# P15-EXP_IO.net
KiCad netlist of a schematic drawn in Altium Designer
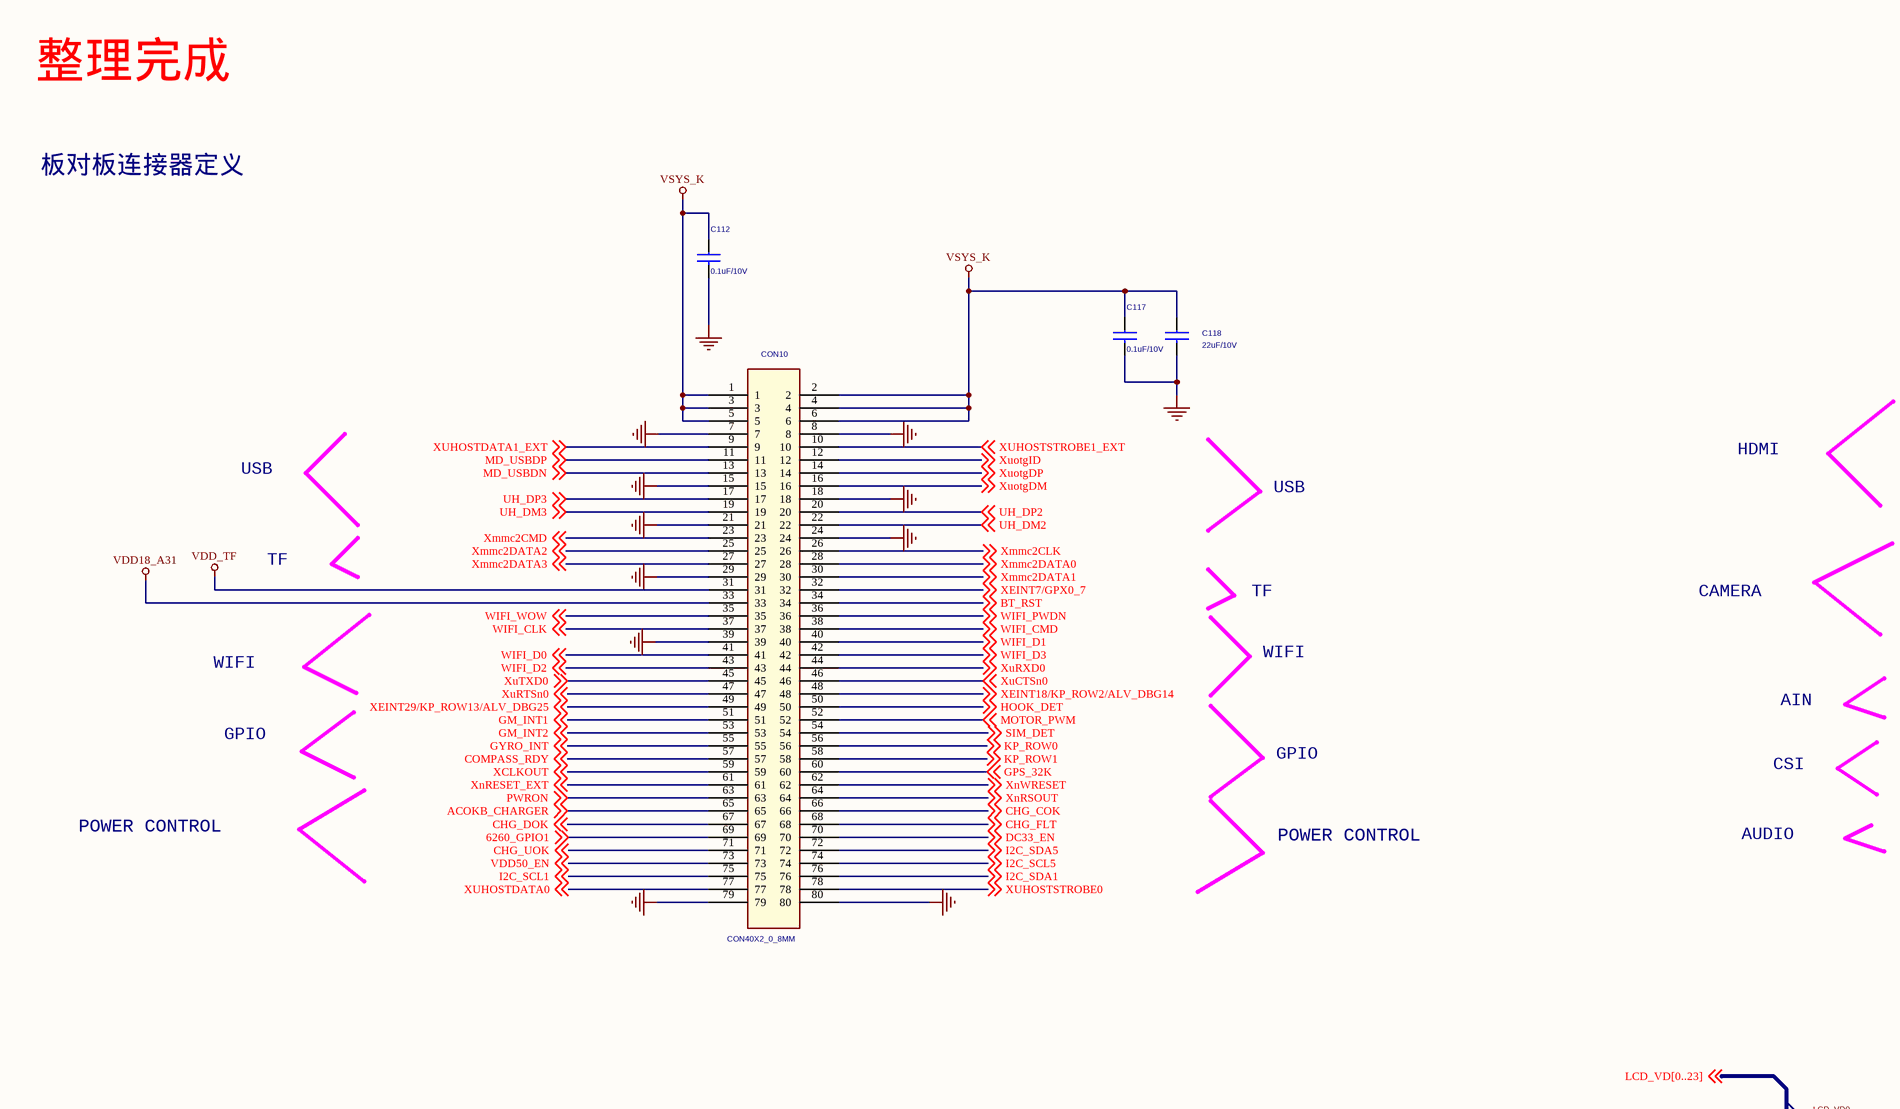
[diagram p0: P15-EXP_IO.SchDoc, top left]
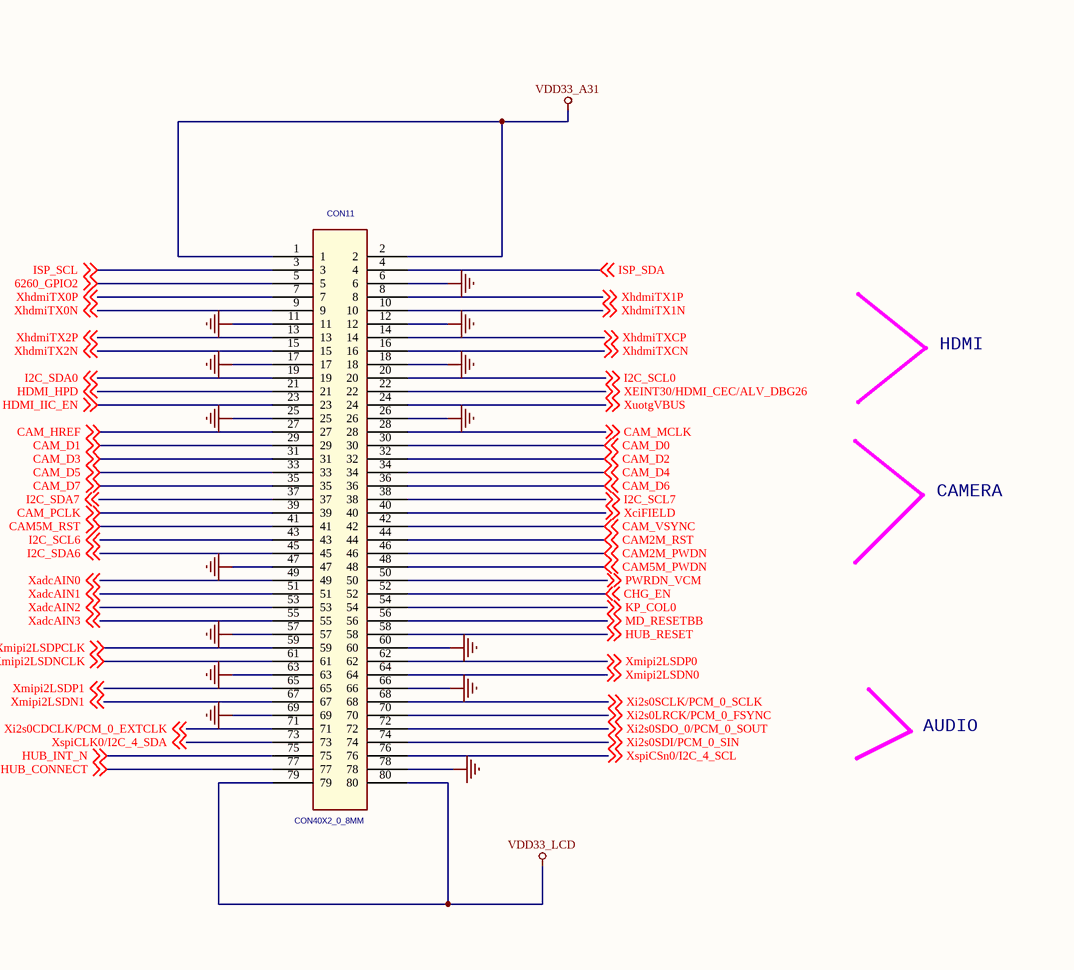
[diagram p1: P15-EXP_IO.SchDoc, top right]
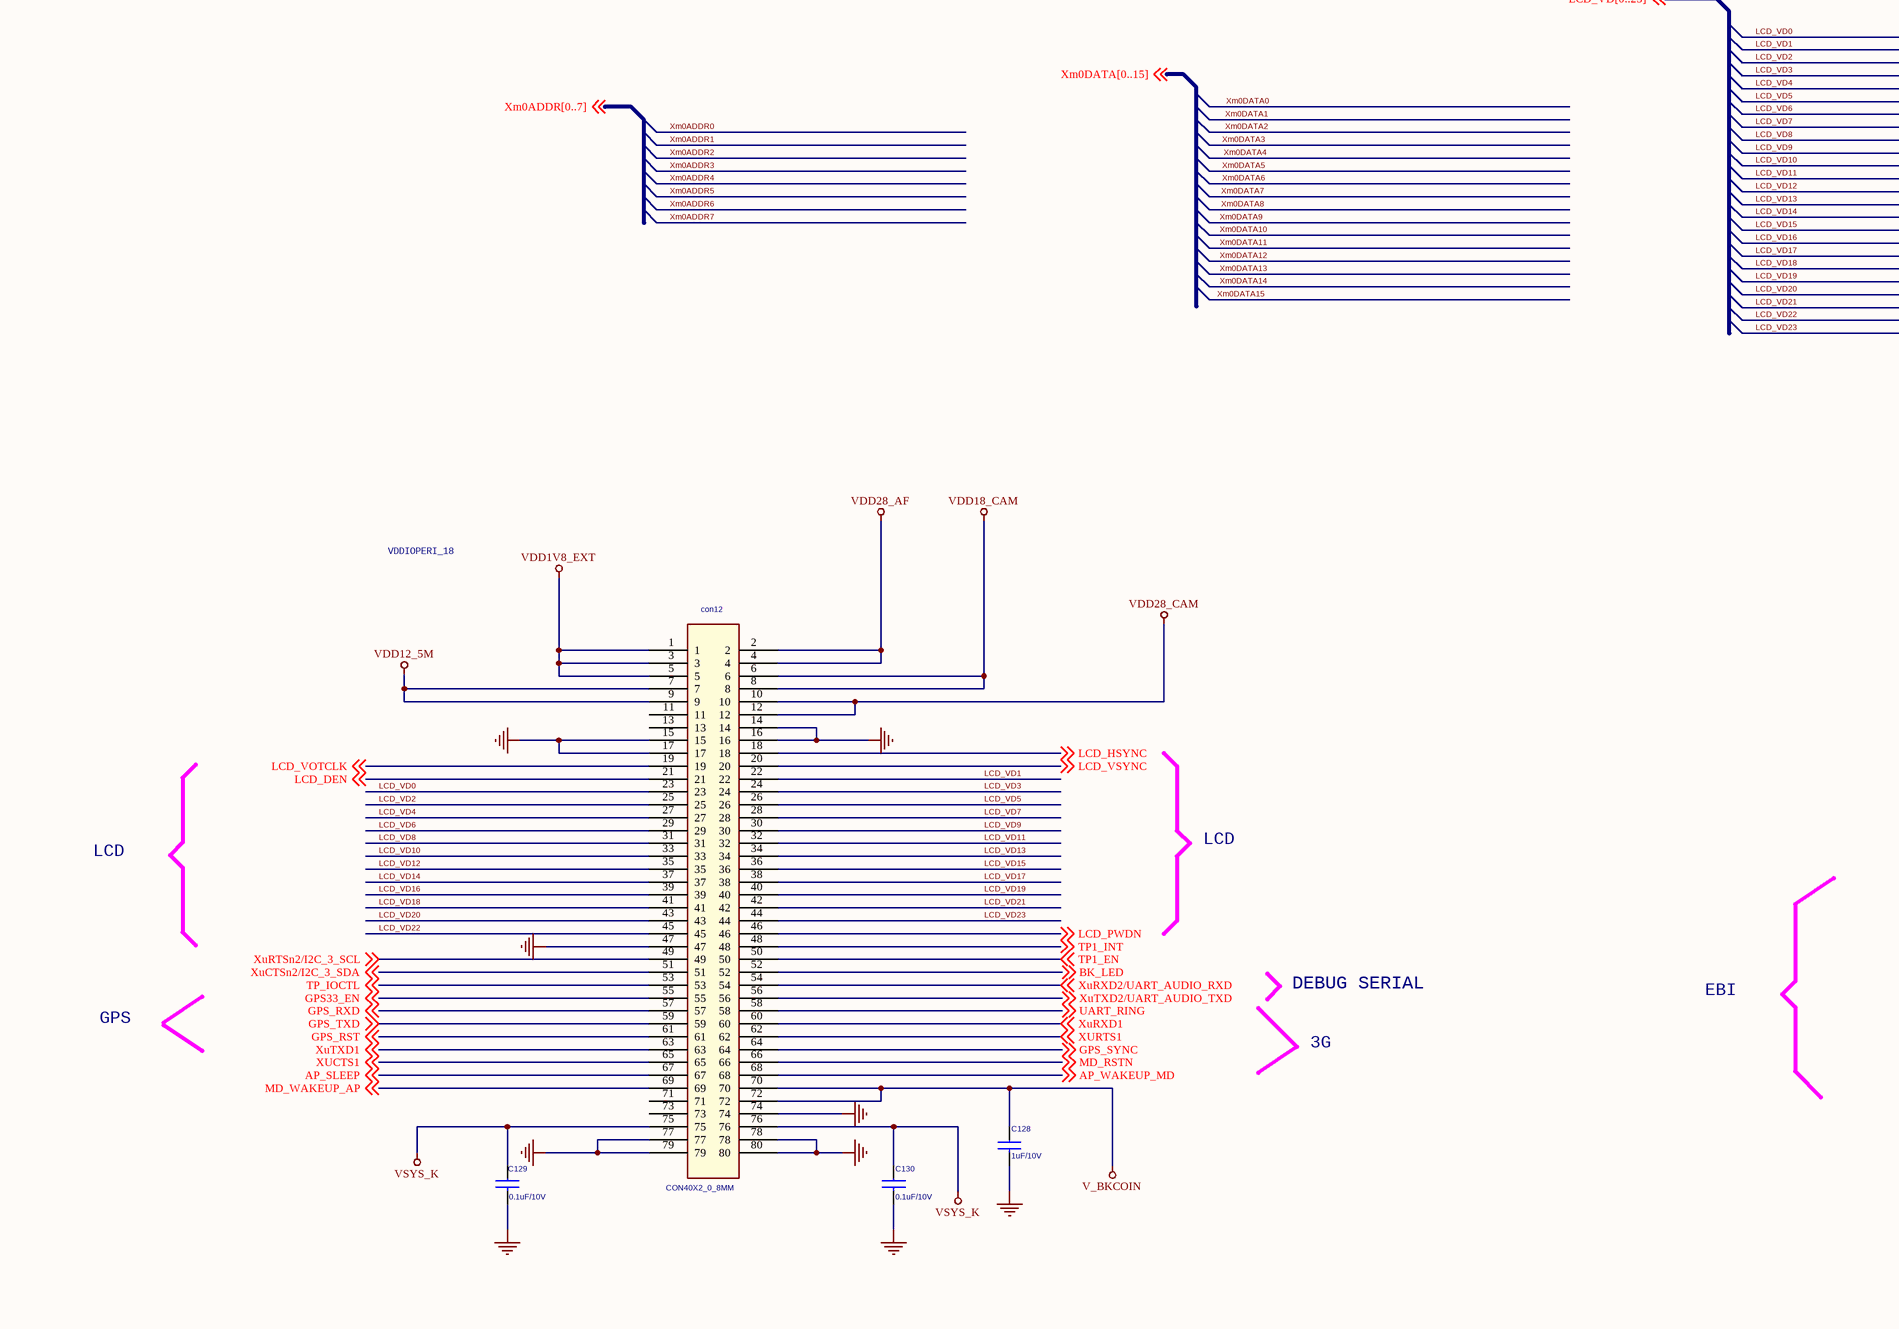
[diagram p2: P15-EXP_IO.SchDoc, bottom left]
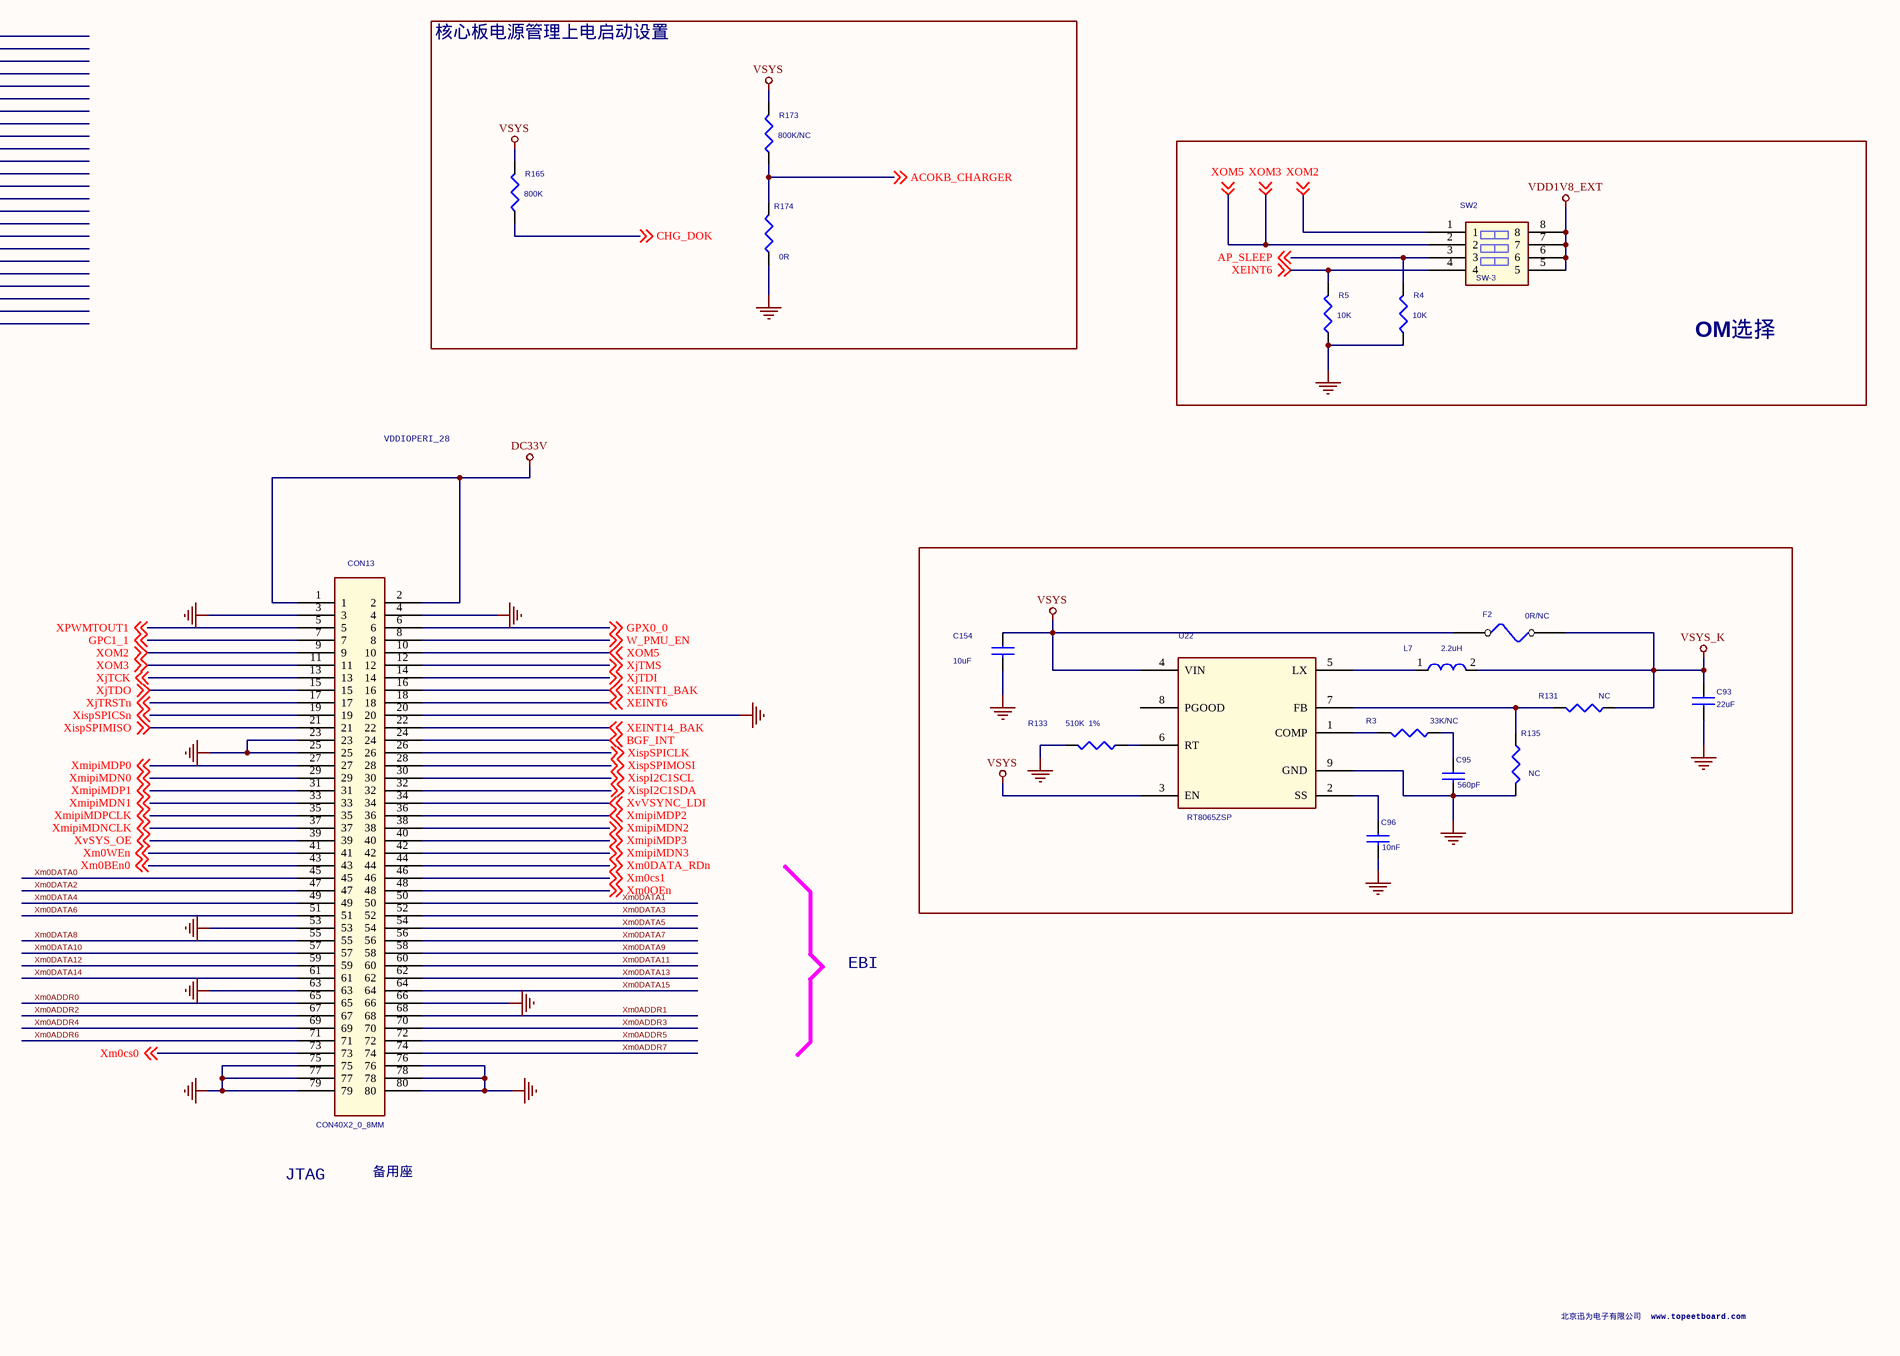
[diagram p3: P15-EXP_IO.SchDoc, bottom right]

(export (version "E")
  (design (tool "Eeschema 10.0.6"))
  (components
    (comp (ref "C93") (value "22uF") (footprint "C0805-S") (libsource (lib "*") (part "C1005")))
    (comp (ref "C95")
      (value "560pF")
      (footprint "C0603-S")
      (description "CER CHIP 1U 10% X5R 0402 10V  L/F")
      (fields (field (name "PART_NUMBER") "06-210594-01"))
      (libsource (lib "*") (part "CAP NP_3"))
    )
    (comp (ref "C96")
      (value "10nF")
      (footprint "C0603-S")
      (description "CER CHIP 1U 10% X5R 0402 10V  L/F")
      (fields (field (name "PART_NUMBER") "06-210594-01"))
      (libsource (lib "*") (part "CAP NP_3"))
    )
    (comp (ref "C112") (value "0.1uF/10V") (footprint "C0603-S") (libsource (lib "*") (part "C0402_0")))
    (comp (ref "C117") (value "0.1uF/10V") (footprint "C0603-S") (libsource (lib "*") (part "C0402_0")))
    (comp (ref "C118") (value "22uF/10V") (footprint "C1206-S") (libsource (lib "*") (part "C1206_0")))
    (comp (ref "C128") (value "1uF/10V") (footprint "C0603-S") (libsource (lib "*") (part "C0603_0")))
    (comp (ref "C129") (value "0.1uF/10V") (footprint "C0603-S") (libsource (lib "*") (part "C0402_0")))
    (comp (ref "C130") (value "0.1uF/10V") (footprint "C0603-S") (libsource (lib "*") (part "C0402_0")))
    (comp (ref "C154")
      (value "10uF")
      (footprint "C0603-S")
      (description "CER CHIP 1U 10% X5R 0402 10V  L/F")
      (fields (field (name "PART_NUMBER") "06-210594-01"))
      (libsource (lib "*") (part "CAP NP_3"))
    )
    (comp (ref "CON10") (value "CON40X2_0_8MM") (libsource (lib "*") (part "CON40X2_0_8MM")))
    (comp (ref "CON11") (value "CON40X2_0_8MM") (libsource (lib "*") (part "CON40X2_0_8MM")))
    (comp (ref "con12")
      (value "CON40X2_0_8MM")
      (footprint "CON2X40-0_5MM-BB")
      (libsource (lib "*") (part "CON40X2_0_8MM"))
    )
    (comp (ref "CON13") (value "CON40X2_0_8MM") (libsource (lib "*") (part "CON40X2_0_8MM")))
    (comp (ref "F2") (value "0R/NC") (libsource (lib "*") (part "FUSE")))
    (comp (ref "L7") (value "2.2uH") (footprint "L3X3MM") (libsource (lib "*") (part "LQH32C_0")))
    (comp (ref "R3") (value "33K/NC") (footprint "R0603-S") (libsource (lib "*") (part "R1005_0")))
    (comp (ref "R4") (value "10K") (footprint "R0603-S") (libsource (lib "*") (part "R1005_0_Dup1")))
    (comp (ref "R5") (value "10K") (footprint "R0603-S") (libsource (lib "*") (part "R1005_0_Dup1")))
    (comp (ref "R131") (value "NC") (footprint "R0603-S") (libsource (lib "*") (part "R1005_0")))
    (comp (ref "R133") (value "510K  1%") (footprint "R0603-S") (libsource (lib "*") (part "R1005_0")))
    (comp (ref "R135") (value "NC") (footprint "R0603-S") (libsource (lib "*") (part "R1005_0")))
    (comp (ref "R165") (value "800K") (footprint "R0603-S") (libsource (lib "*") (part "R1005_0_Dup1")))
    (comp (ref "R173") (value "800K/NC") (footprint "R0603-S") (libsource (lib "*") (part "R1005_0_Dup1")))
    (comp (ref "R174") (value "0R") (footprint "R0603-S") (libsource (lib "*") (part "R1005_0_Dup1")))
    (comp (ref "SW2") (value "SW-3") (libsource (lib "*") (part "SW-3_1")))
    (comp (ref "U22") (value "RT8065ZSP") (libsource (lib "*") (part "RT8065_3")))
  )
  (nets
    (net (code "1") (name "6260_GPIO1") (class "Default")
      (node (ref "CON10") (pin "69") (pinfunction "69_69") (pintype "passive"))
    )
    (net (code "2") (name "6260_GPIO2") (class "Default")
      (node (ref "CON11") (pin "5") (pinfunction "5_5") (pintype "passive"))
    )
    (net (code "3") (name "ACOKB_CHARGER") (class "Default")
      (node (ref "CON10") (pin "65") (pinfunction "65_65") (pintype "passive"))
      (node (ref "R173") (pin "1") (pinfunction "1_1") (pintype "passive"))
      (node (ref "R174") (pin "2") (pinfunction "2_2") (pintype "passive"))
    )
    (net (code "4") (name "AP_SLEEP") (class "Default")
      (node (ref "R4") (pin "2") (pinfunction "2_2") (pintype "passive"))
      (node (ref "SW2") (pin "3") (pinfunction "3_3") (pintype "passive"))
      (node (ref "con12") (pin "67") (pinfunction "67_67") (pintype "passive"))
    )
    (net (code "5") (name "AP_WAKEUP_MD") (class "Default")
      (node (ref "con12") (pin "68") (pinfunction "68_68") (pintype "passive"))
    )
    (net (code "6") (name "BGF_INT") (class "Default")
      (node (ref "CON13") (pin "24") (pinfunction "24_24") (pintype "passive"))
    )
    (net (code "7") (name "BK_LED") (class "Default")
      (node (ref "con12") (pin "52") (pinfunction "52_52") (pintype "passive"))
    )
    (net (code "8") (name "BT_RST") (class "Default")
      (node (ref "CON10") (pin "34") (pinfunction "34_34") (pintype "passive"))
    )
    (net (code "9") (name "CAM2M_PWDN") (class "Default")
      (node (ref "CON11") (pin "46") (pinfunction "46_46") (pintype "passive"))
    )
    (net (code "10") (name "CAM2M_RST") (class "Default")
      (node (ref "CON11") (pin "44") (pinfunction "44_44") (pintype "passive"))
    )
    (net (code "11") (name "CAM5M_PWDN") (class "Default")
      (node (ref "CON11") (pin "48") (pinfunction "48_48") (pintype "passive"))
    )
    (net (code "12") (name "CAM5M_RST") (class "Default")
      (node (ref "CON11") (pin "41") (pinfunction "41_41") (pintype "passive"))
    )
    (net (code "13") (name "CAM_D0") (class "Default")
      (node (ref "CON11") (pin "30") (pinfunction "30_30") (pintype "passive"))
    )
    (net (code "14") (name "CAM_D1") (class "Default")
      (node (ref "CON11") (pin "29") (pinfunction "29_29") (pintype "passive"))
    )
    (net (code "15") (name "CAM_D2") (class "Default")
      (node (ref "CON11") (pin "32") (pinfunction "32_32") (pintype "passive"))
    )
    (net (code "16") (name "CAM_D3") (class "Default")
      (node (ref "CON11") (pin "31") (pinfunction "31_31") (pintype "passive"))
    )
    (net (code "17") (name "CAM_D4") (class "Default")
      (node (ref "CON11") (pin "34") (pinfunction "34_34") (pintype "passive"))
    )
    (net (code "18") (name "CAM_D5") (class "Default")
      (node (ref "CON11") (pin "33") (pinfunction "33_33") (pintype "passive"))
    )
    (net (code "19") (name "CAM_D6") (class "Default")
      (node (ref "CON11") (pin "36") (pinfunction "36_36") (pintype "passive"))
    )
    (net (code "20") (name "CAM_D7") (class "Default")
      (node (ref "CON11") (pin "35") (pinfunction "35_35") (pintype "passive"))
    )
    (net (code "21") (name "CAM_HREF") (class "Default")
      (node (ref "CON11") (pin "27") (pinfunction "27_27") (pintype "passive"))
    )
    (net (code "22") (name "CAM_MCLK") (class "Default")
      (node (ref "CON11") (pin "28") (pinfunction "28_28") (pintype "passive"))
    )
    (net (code "23") (name "CAM_PCLK") (class "Default")
      (node (ref "CON11") (pin "39") (pinfunction "39_39") (pintype "passive"))
    )
    (net (code "24") (name "CAM_VSYNC") (class "Default")
      (node (ref "CON11") (pin "42") (pinfunction "42_42") (pintype "passive"))
    )
    (net (code "25") (name "CHG_COK") (class "Default")
      (node (ref "CON10") (pin "66") (pinfunction "66_66") (pintype "passive"))
    )
    (net (code "26") (name "CHG_DOK") (class "Default")
      (node (ref "CON10") (pin "67") (pinfunction "67_67") (pintype "passive"))
      (node (ref "R165") (pin "1") (pinfunction "1_1") (pintype "passive"))
    )
    (net (code "27") (name "CHG_EN") (class "Default")
      (node (ref "CON11") (pin "52") (pinfunction "52_52") (pintype "passive"))
    )
    (net (code "28") (name "CHG_FLT") (class "Default")
      (node (ref "CON10") (pin "68") (pinfunction "68_68") (pintype "passive"))
    )
    (net (code "29") (name "CHG_UOK") (class "Default")
      (node (ref "CON10") (pin "71") (pinfunction "71_71") (pintype "passive"))
    )
    (net (code "30") (name "COMPASS_RDY") (class "Default")
      (node (ref "CON10") (pin "57") (pinfunction "57_57") (pintype "passive"))
    )
    (net (code "31") (name "DC33V") (class "Default")
      (node (ref "CON13") (pin "1") (pinfunction "1_1") (pintype "passive"))
      (node (ref "CON13") (pin "2") (pinfunction "2_2") (pintype "passive"))
    )
    (net (code "32") (name "DC33_EN") (class "Default")
      (node (ref "CON10") (pin "70") (pinfunction "70_70") (pintype "passive"))
    )
    (net (code "33") (name "GM_INT1") (class "Default")
      (node (ref "CON10") (pin "51") (pinfunction "51_51") (pintype "passive"))
    )
    (net (code "34") (name "GM_INT2") (class "Default")
      (node (ref "CON10") (pin "53") (pinfunction "53_53") (pintype "passive"))
    )
    (net (code "35") (name "GND") (class "Default")
      (node (ref "C112") (pin "2") (pinfunction "2_2") (pintype "passive"))
      (node (ref "C117") (pin "2") (pinfunction "2_2") (pintype "passive"))
      (node (ref "C118") (pin "2") (pinfunction "2_2") (pintype "passive"))
      (node (ref "C128") (pin "2") (pinfunction "2_2") (pintype "passive"))
      (node (ref "C129") (pin "2") (pinfunction "2_2") (pintype "passive"))
      (node (ref "C130") (pin "2") (pinfunction "2_2") (pintype "passive"))
      (node (ref "C154") (pin "2") (pinfunction "2_2") (pintype "passive"))
      (node (ref "C93") (pin "2") (pinfunction "2_2") (pintype "passive"))
      (node (ref "C95") (pin "2") (pinfunction "2_2") (pintype "passive"))
      (node (ref "C96") (pin "2") (pinfunction "2_2") (pintype "passive"))
      (node (ref "CON10") (pin "15") (pinfunction "15_15") (pintype "passive"))
      (node (ref "CON10") (pin "18") (pinfunction "18_18") (pintype "passive"))
      (node (ref "CON10") (pin "21") (pinfunction "21_21") (pintype "passive"))
      (node (ref "CON10") (pin "24") (pinfunction "24_24") (pintype "passive"))
      (node (ref "CON10") (pin "29") (pinfunction "29_29") (pintype "passive"))
      (node (ref "CON10") (pin "39") (pinfunction "39_39") (pintype "passive"))
      (node (ref "CON10") (pin "7") (pinfunction "7_7") (pintype "passive"))
      (node (ref "CON10") (pin "79") (pinfunction "79_79") (pintype "passive"))
      (node (ref "CON10") (pin "8") (pinfunction "8_8") (pintype "passive"))
      (node (ref "CON10") (pin "80") (pinfunction "80_80") (pintype "passive"))
      (node (ref "CON11") (pin "11") (pinfunction "11_11") (pintype "passive"))
      (node (ref "CON11") (pin "12") (pinfunction "12_12") (pintype "passive"))
      (node (ref "CON11") (pin "17") (pinfunction "17_17") (pintype "passive"))
      (node (ref "CON11") (pin "18") (pinfunction "18_18") (pintype "passive"))
      (node (ref "CON11") (pin "25") (pinfunction "25_25") (pintype "passive"))
      (node (ref "CON11") (pin "26") (pinfunction "26_26") (pintype "passive"))
      (node (ref "CON11") (pin "47") (pinfunction "47_47") (pintype "passive"))
      (node (ref "CON11") (pin "57") (pinfunction "57_57") (pintype "passive"))
      (node (ref "CON11") (pin "6") (pinfunction "6_6") (pintype "passive"))
      (node (ref "CON11") (pin "60") (pinfunction "60_60") (pintype "passive"))
      (node (ref "CON11") (pin "63") (pinfunction "63_63") (pintype "passive"))
      (node (ref "CON11") (pin "66") (pinfunction "66_66") (pintype "passive"))
      (node (ref "CON11") (pin "69") (pinfunction "69_69") (pintype "passive"))
      (node (ref "CON11") (pin "78") (pinfunction "78_78") (pintype "passive"))
      (node (ref "CON13") (pin "20") (pinfunction "20_20") (pintype "passive"))
      (node (ref "CON13") (pin "23") (pinfunction "23_23") (pintype "passive"))
      (node (ref "CON13") (pin "25") (pinfunction "25_25") (pintype "passive"))
      (node (ref "CON13") (pin "3") (pinfunction "3_3") (pintype "passive"))
      (node (ref "CON13") (pin "4") (pinfunction "4_4") (pintype "passive"))
      (node (ref "CON13") (pin "53") (pinfunction "53_53") (pintype "passive"))
      (node (ref "CON13") (pin "63") (pinfunction "63_63") (pintype "passive"))
      (node (ref "CON13") (pin "66") (pinfunction "66_66") (pintype "passive"))
      (node (ref "CON13") (pin "75") (pinfunction "75_75") (pintype "passive"))
      (node (ref "CON13") (pin "76") (pinfunction "76_76") (pintype "passive"))
      (node (ref "CON13") (pin "77") (pinfunction "77_77") (pintype "passive"))
      (node (ref "CON13") (pin "78") (pinfunction "78_78") (pintype "passive"))
      (node (ref "CON13") (pin "79") (pinfunction "79_79") (pintype "passive"))
      (node (ref "CON13") (pin "80") (pinfunction "80_80") (pintype "passive"))
      (node (ref "R133") (pin "2") (pinfunction "2_2") (pintype "passive"))
      (node (ref "R135") (pin "2") (pinfunction "2_2") (pintype "passive"))
      (node (ref "R174") (pin "1") (pinfunction "1_1") (pintype "passive"))
      (node (ref "R4") (pin "1") (pinfunction "1_1") (pintype "passive"))
      (node (ref "R5") (pin "1") (pinfunction "1_1") (pintype "passive"))
      (node (ref "U22") (pin "9") (pinfunction "GND_9") (pintype "passive"))
      (node (ref "con12") (pin "14") (pinfunction "14_14") (pintype "passive"))
      (node (ref "con12") (pin "15") (pinfunction "15_15") (pintype "passive"))
      (node (ref "con12") (pin "16") (pinfunction "16_16") (pintype "passive"))
      (node (ref "con12") (pin "17") (pinfunction "17_17") (pintype "passive"))
      (node (ref "con12") (pin "47") (pinfunction "47_47") (pintype "passive"))
      (node (ref "con12") (pin "74") (pinfunction "74_74") (pintype "passive"))
      (node (ref "con12") (pin "77") (pinfunction "77_77") (pintype "passive"))
      (node (ref "con12") (pin "78") (pinfunction "78_78") (pintype "passive"))
      (node (ref "con12") (pin "79") (pinfunction "79_79") (pintype "passive"))
      (node (ref "con12") (pin "80") (pinfunction "80_80") (pintype "passive"))
    )
    (net (code "36") (name "GPC1_1") (class "Default")
      (node (ref "CON13") (pin "7") (pinfunction "7_7") (pintype "passive"))
    )
    (net (code "37") (name "GPS33_EN") (class "Default")
      (node (ref "con12") (pin "55") (pinfunction "55_55") (pintype "passive"))
    )
    (net (code "38") (name "GPS_32K") (class "Default")
      (node (ref "CON10") (pin "60") (pinfunction "60_60") (pintype "passive"))
    )
    (net (code "39") (name "GPS_RST") (class "Default")
      (node (ref "con12") (pin "61") (pinfunction "61_61") (pintype "passive"))
    )
    (net (code "40") (name "GPS_RXD") (class "Default")
      (node (ref "con12") (pin "57") (pinfunction "57_57") (pintype "passive"))
    )
    (net (code "41") (name "GPS_SYNC") (class "Default")
      (node (ref "con12") (pin "64") (pinfunction "64_64") (pintype "passive"))
    )
    (net (code "42") (name "GPS_TXD") (class "Default")
      (node (ref "con12") (pin "59") (pinfunction "59_59") (pintype "passive"))
    )
    (net (code "43") (name "GPX0_0") (class "Default")
      (node (ref "CON13") (pin "6") (pinfunction "6_6") (pintype "passive"))
    )
    (net (code "44") (name "GYRO_INT") (class "Default")
      (node (ref "CON10") (pin "55") (pinfunction "55_55") (pintype "passive"))
    )
    (net (code "45") (name "HDMI_HPD") (class "Default")
      (node (ref "CON11") (pin "21") (pinfunction "21_21") (pintype "passive"))
    )
    (net (code "46") (name "HDMI_IIC_EN") (class "Default")
      (node (ref "CON11") (pin "23") (pinfunction "23_23") (pintype "passive"))
    )
    (net (code "47") (name "HOOK_DET") (class "Default")
      (node (ref "CON10") (pin "50") (pinfunction "50_50") (pintype "passive"))
    )
    (net (code "48") (name "HUB_CONNECT") (class "Default")
      (node (ref "CON11") (pin "77") (pinfunction "77_77") (pintype "passive"))
    )
    (net (code "49") (name "HUB_INT_N") (class "Default")
      (node (ref "CON11") (pin "75") (pinfunction "75_75") (pintype "passive"))
    )
    (net (code "50") (name "HUB_RESET") (class "Default")
      (node (ref "CON11") (pin "58") (pinfunction "58_58") (pintype "passive"))
    )
    (net (code "51") (name "I2C_SCL0") (class "Default")
      (node (ref "CON11") (pin "20") (pinfunction "20_20") (pintype "passive"))
    )
    (net (code "52") (name "I2C_SCL1") (class "Default")
      (node (ref "CON10") (pin "75") (pinfunction "75_75") (pintype "passive"))
    )
    (net (code "53") (name "I2C_SCL5") (class "Default")
      (node (ref "CON10") (pin "74") (pinfunction "74_74") (pintype "passive"))
    )
    (net (code "54") (name "I2C_SCL6") (class "Default")
      (node (ref "CON11") (pin "43") (pinfunction "43_43") (pintype "passive"))
    )
    (net (code "55") (name "I2C_SCL7") (class "Default")
      (node (ref "CON11") (pin "38") (pinfunction "38_38") (pintype "passive"))
    )
    (net (code "56") (name "I2C_SDA0") (class "Default")
      (node (ref "CON11") (pin "19") (pinfunction "19_19") (pintype "passive"))
    )
    (net (code "57") (name "I2C_SDA1") (class "Default")
      (node (ref "CON10") (pin "76") (pinfunction "76_76") (pintype "passive"))
    )
    (net (code "58") (name "I2C_SDA5") (class "Default")
      (node (ref "CON10") (pin "72") (pinfunction "72_72") (pintype "passive"))
    )
    (net (code "59") (name "I2C_SDA6") (class "Default")
      (node (ref "CON11") (pin "45") (pinfunction "45_45") (pintype "passive"))
    )
    (net (code "60") (name "I2C_SDA7") (class "Default")
      (node (ref "CON11") (pin "37") (pinfunction "37_37") (pintype "passive"))
    )
    (net (code "61") (name "ISP_SCL") (class "Default")
      (node (ref "CON11") (pin "3") (pinfunction "3_3") (pintype "passive"))
    )
    (net (code "62") (name "ISP_SDA") (class "Default")
      (node (ref "CON11") (pin "4") (pinfunction "4_4") (pintype "passive"))
    )
    (net (code "63") (name "KP_COL0") (class "Default")
      (node (ref "CON11") (pin "54") (pinfunction "54_54") (pintype "passive"))
    )
    (net (code "64") (name "KP_ROW0") (class "Default")
      (node (ref "CON10") (pin "56") (pinfunction "56_56") (pintype "passive"))
    )
    (net (code "65") (name "KP_ROW1") (class "Default")
      (node (ref "CON10") (pin "58") (pinfunction "58_58") (pintype "passive"))
    )
    (net (code "66") (name "LCD_DEN") (class "Default")
      (node (ref "con12") (pin "21") (pinfunction "21_21") (pintype "passive"))
    )
    (net (code "67") (name "LCD_HSYNC") (class "Default")
      (node (ref "con12") (pin "18") (pinfunction "18_18") (pintype "passive"))
    )
    (net (code "68") (name "LCD_PWDN") (class "Default")
      (node (ref "con12") (pin "46") (pinfunction "46_46") (pintype "passive"))
    )
    (net (code "69") (name "LCD_VD0") (class "Default")
      (node (ref "con12") (pin "23") (pinfunction "23_23") (pintype "passive"))
    )
    (net (code "70") (name "LCD_VD1") (class "Default")
      (node (ref "con12") (pin "22") (pinfunction "22_22") (pintype "passive"))
    )
    (net (code "71") (name "LCD_VD2") (class "Default")
      (node (ref "con12") (pin "25") (pinfunction "25_25") (pintype "passive"))
    )
    (net (code "72") (name "LCD_VD3") (class "Default")
      (node (ref "con12") (pin "24") (pinfunction "24_24") (pintype "passive"))
    )
    (net (code "73") (name "LCD_VD4") (class "Default")
      (node (ref "con12") (pin "27") (pinfunction "27_27") (pintype "passive"))
    )
    (net (code "74") (name "LCD_VD5") (class "Default")
      (node (ref "con12") (pin "26") (pinfunction "26_26") (pintype "passive"))
    )
    (net (code "75") (name "LCD_VD6") (class "Default")
      (node (ref "con12") (pin "29") (pinfunction "29_29") (pintype "passive"))
    )
    (net (code "76") (name "LCD_VD7") (class "Default")
      (node (ref "con12") (pin "28") (pinfunction "28_28") (pintype "passive"))
    )
    (net (code "77") (name "LCD_VD8") (class "Default")
      (node (ref "con12") (pin "31") (pinfunction "31_31") (pintype "passive"))
    )
    (net (code "78") (name "LCD_VD9") (class "Default")
      (node (ref "con12") (pin "30") (pinfunction "30_30") (pintype "passive"))
    )
    (net (code "79") (name "LCD_VD10") (class "Default")
      (node (ref "con12") (pin "33") (pinfunction "33_33") (pintype "passive"))
    )
    (net (code "80") (name "LCD_VD11") (class "Default")
      (node (ref "con12") (pin "32") (pinfunction "32_32") (pintype "passive"))
    )
    (net (code "81") (name "LCD_VD12") (class "Default")
      (node (ref "con12") (pin "35") (pinfunction "35_35") (pintype "passive"))
    )
    (net (code "82") (name "LCD_VD13") (class "Default")
      (node (ref "con12") (pin "34") (pinfunction "34_34") (pintype "passive"))
    )
    (net (code "83") (name "LCD_VD14") (class "Default")
      (node (ref "con12") (pin "37") (pinfunction "37_37") (pintype "passive"))
    )
    (net (code "84") (name "LCD_VD15") (class "Default")
      (node (ref "con12") (pin "36") (pinfunction "36_36") (pintype "passive"))
    )
    (net (code "85") (name "LCD_VD16") (class "Default")
      (node (ref "con12") (pin "39") (pinfunction "39_39") (pintype "passive"))
    )
    (net (code "86") (name "LCD_VD17") (class "Default")
      (node (ref "con12") (pin "38") (pinfunction "38_38") (pintype "passive"))
    )
    (net (code "87") (name "LCD_VD18") (class "Default")
      (node (ref "con12") (pin "41") (pinfunction "41_41") (pintype "passive"))
    )
    (net (code "88") (name "LCD_VD19") (class "Default")
      (node (ref "con12") (pin "40") (pinfunction "40_40") (pintype "passive"))
    )
    (net (code "89") (name "LCD_VD20") (class "Default")
      (node (ref "con12") (pin "43") (pinfunction "43_43") (pintype "passive"))
    )
    (net (code "90") (name "LCD_VD21") (class "Default")
      (node (ref "con12") (pin "42") (pinfunction "42_42") (pintype "passive"))
    )
    (net (code "91") (name "LCD_VD22") (class "Default")
      (node (ref "con12") (pin "45") (pinfunction "45_45") (pintype "passive"))
    )
    (net (code "92") (name "LCD_VD23") (class "Default")
      (node (ref "con12") (pin "44") (pinfunction "44_44") (pintype "passive"))
    )
    (net (code "94") (name "LCD_VOTCLK") (class "Default")
      (node (ref "con12") (pin "19") (pinfunction "19_19") (pintype "passive"))
    )
    (net (code "95") (name "LCD_VSYNC") (class "Default")
      (node (ref "con12") (pin "20") (pinfunction "20_20") (pintype "passive"))
    )
    (net (code "96") (name "MD_RESETBB") (class "Default")
      (node (ref "CON11") (pin "56") (pinfunction "56_56") (pintype "passive"))
    )
    (net (code "97") (name "MD_RSTN") (class "Default")
      (node (ref "con12") (pin "66") (pinfunction "66_66") (pintype "passive"))
    )
    (net (code "98") (name "MD_USBDN") (class "Default")
      (node (ref "CON10") (pin "13") (pinfunction "13_13") (pintype "passive"))
    )
    (net (code "99") (name "MD_USBDP") (class "Default")
      (node (ref "CON10") (pin "11") (pinfunction "11_11") (pintype "passive"))
    )
    (net (code "100") (name "MD_WAKEUP_AP") (class "Default")
      (node (ref "con12") (pin "69") (pinfunction "69_69") (pintype "passive"))
    )
    (net (code "101") (name "MOTOR_PWM") (class "Default")
      (node (ref "CON10") (pin "52") (pinfunction "52_52") (pintype "passive"))
    )
    (net (code "102") (name "Net-(C95-Pad1)") (class "Default")
      (node (ref "C95") (pin "1") (pinfunction "1_1") (pintype "passive"))
      (node (ref "R3") (pin "1") (pinfunction "1_1") (pintype "passive"))
    )
    (net (code "103") (name "Net-(U22-COMP)") (class "Default")
      (node (ref "R3") (pin "2") (pinfunction "2_2") (pintype "passive"))
      (node (ref "U22") (pin "1") (pinfunction "COMP_1") (pintype "passive"))
    )
    (net (code "104") (name "Net-(U22-FB)") (class "Default")
      (node (ref "R131") (pin "2") (pinfunction "2_2") (pintype "passive"))
      (node (ref "R135") (pin "1") (pinfunction "1_1") (pintype "passive"))
      (node (ref "U22") (pin "7") (pinfunction "FB_7") (pintype "passive"))
    )
    (net (code "105") (name "Net-(U22-LX)") (class "Default")
      (node (ref "L7") (pin "1") (pinfunction "1_1") (pintype "passive"))
      (node (ref "U22") (pin "5") (pinfunction "LX_5") (pintype "passive"))
    )
    (net (code "106") (name "Net-(U22-RT)") (class "Default")
      (node (ref "R133") (pin "1") (pinfunction "1_1") (pintype "passive"))
      (node (ref "U22") (pin "6") (pinfunction "RT_6") (pintype "passive"))
    )
    (net (code "107") (name "Net-(U22-SS)") (class "Default")
      (node (ref "C96") (pin "1") (pinfunction "1_1") (pintype "passive"))
      (node (ref "U22") (pin "2") (pinfunction "SS_2") (pintype "passive"))
    )
    (net (code "108") (name "PWRDN_VCM") (class "Default")
      (node (ref "CON11") (pin "50") (pinfunction "50_50") (pintype "passive"))
    )
    (net (code "109") (name "PWRON") (class "Default")
      (node (ref "CON10") (pin "63") (pinfunction "63_63") (pintype "passive"))
    )
    (net (code "110") (name "SIM_DET") (class "Default")
      (node (ref "CON10") (pin "54") (pinfunction "54_54") (pintype "passive"))
    )
    (net (code "111") (name "TP1_EN") (class "Default")
      (node (ref "con12") (pin "50") (pinfunction "50_50") (pintype "passive"))
    )
    (net (code "112") (name "TP1_INT") (class "Default")
      (node (ref "con12") (pin "48") (pinfunction "48_48") (pintype "passive"))
    )
    (net (code "113") (name "TP_IOCTL") (class "Default")
      (node (ref "con12") (pin "53") (pinfunction "53_53") (pintype "passive"))
    )
    (net (code "114") (name "UART_RING") (class "Default")
      (node (ref "con12") (pin "58") (pinfunction "58_58") (pintype "passive"))
    )
    (net (code "115") (name "UH_DM2") (class "Default")
      (node (ref "CON10") (pin "22") (pinfunction "22_22") (pintype "passive"))
    )
    (net (code "116") (name "UH_DM3") (class "Default")
      (node (ref "CON10") (pin "19") (pinfunction "19_19") (pintype "passive"))
    )
    (net (code "117") (name "UH_DP2") (class "Default")
      (node (ref "CON10") (pin "20") (pinfunction "20_20") (pintype "passive"))
    )
    (net (code "118") (name "UH_DP3") (class "Default")
      (node (ref "CON10") (pin "17") (pinfunction "17_17") (pintype "passive"))
    )
    (net (code "119") (name "VDD1V8_EXT") (class "Default")
      (node (ref "SW2") (pin "5") (pinfunction "5_5") (pintype "passive"))
      (node (ref "SW2") (pin "6") (pinfunction "6_6") (pintype "passive"))
      (node (ref "SW2") (pin "7") (pinfunction "7_7") (pintype "passive"))
      (node (ref "SW2") (pin "8") (pinfunction "8_8") (pintype "passive"))
      (node (ref "con12") (pin "1") (pinfunction "1_1") (pintype "passive"))
      (node (ref "con12") (pin "3") (pinfunction "3_3") (pintype "passive"))
      (node (ref "con12") (pin "5") (pinfunction "5_5") (pintype "passive"))
    )
    (net (code "120") (name "VDD12_5M") (class "Default")
      (node (ref "con12") (pin "7") (pinfunction "7_7") (pintype "passive"))
      (node (ref "con12") (pin "9") (pinfunction "9_9") (pintype "passive"))
    )
    (net (code "121") (name "VDD18_A31") (class "Default")
      (node (ref "CON10") (pin "33") (pinfunction "33_33") (pintype "passive"))
    )
    (net (code "122") (name "VDD18_CAM") (class "Default")
      (node (ref "con12") (pin "6") (pinfunction "6_6") (pintype "passive"))
      (node (ref "con12") (pin "8") (pinfunction "8_8") (pintype "passive"))
    )
    (net (code "123") (name "VDD28_AF") (class "Default")
      (node (ref "con12") (pin "2") (pinfunction "2_2") (pintype "passive"))
      (node (ref "con12") (pin "4") (pinfunction "4_4") (pintype "passive"))
    )
    (net (code "124") (name "VDD28_CAM") (class "Default")
      (node (ref "con12") (pin "10") (pinfunction "10_10") (pintype "passive"))
      (node (ref "con12") (pin "12") (pinfunction "12_12") (pintype "passive"))
    )
    (net (code "125") (name "VDD33_A31") (class "Default")
      (node (ref "CON11") (pin "1") (pinfunction "1_1") (pintype "passive"))
      (node (ref "CON11") (pin "2") (pinfunction "2_2") (pintype "passive"))
    )
    (net (code "126") (name "VDD33_LCD") (class "Default")
      (node (ref "CON11") (pin "79") (pinfunction "79_79") (pintype "passive"))
      (node (ref "CON11") (pin "80") (pinfunction "80_80") (pintype "passive"))
    )
    (net (code "127") (name "VDD50_EN") (class "Default")
      (node (ref "CON10") (pin "73") (pinfunction "73_73") (pintype "passive"))
    )
    (net (code "128") (name "VDD_TF") (class "Default")
      (node (ref "CON10") (pin "31") (pinfunction "31_31") (pintype "passive"))
    )
    (net (code "129") (name "VSYS") (class "Default")
      (node (ref "C154") (pin "1") (pinfunction "1_1") (pintype "passive"))
      (node (ref "F2") (pin "1") (pinfunction "1_1") (pintype "passive"))
      (node (ref "R165") (pin "2") (pinfunction "2_2") (pintype "passive"))
      (node (ref "R173") (pin "2") (pinfunction "2_2") (pintype "passive"))
      (node (ref "U22") (pin "3") (pinfunction "EN_3") (pintype "passive"))
      (node (ref "U22") (pin "4") (pinfunction "VIN_4") (pintype "passive"))
    )
    (net (code "130") (name "VSYS_K") (class "Default")
      (node (ref "C112") (pin "1") (pinfunction "1_1") (pintype "passive"))
      (node (ref "C117") (pin "1") (pinfunction "1_1") (pintype "passive"))
      (node (ref "C118") (pin "1") (pinfunction "1_1") (pintype "passive"))
      (node (ref "C129") (pin "1") (pinfunction "1_1") (pintype "passive"))
      (node (ref "C130") (pin "1") (pinfunction "1_1") (pintype "passive"))
      (node (ref "C93") (pin "1") (pinfunction "1_1") (pintype "passive"))
      (node (ref "CON10") (pin "1") (pinfunction "1_1") (pintype "passive"))
      (node (ref "CON10") (pin "2") (pinfunction "2_2") (pintype "passive"))
      (node (ref "CON10") (pin "3") (pinfunction "3_3") (pintype "passive"))
      (node (ref "CON10") (pin "4") (pinfunction "4_4") (pintype "passive"))
      (node (ref "CON10") (pin "5") (pinfunction "5_5") (pintype "passive"))
      (node (ref "CON10") (pin "6") (pinfunction "6_6") (pintype "passive"))
      (node (ref "F2") (pin "2") (pinfunction "2_2") (pintype "passive"))
      (node (ref "L7") (pin "2") (pinfunction "2_2") (pintype "passive"))
      (node (ref "R131") (pin "1") (pinfunction "1_1") (pintype "passive"))
      (node (ref "con12") (pin "75") (pinfunction "75_75") (pintype "passive"))
      (node (ref "con12") (pin "76") (pinfunction "76_76") (pintype "passive"))
    )
    (net (code "131") (name "V_BKCOIN") (class "Default")
      (node (ref "C128") (pin "1") (pinfunction "1_1") (pintype "passive"))
      (node (ref "con12") (pin "70") (pinfunction "70_70") (pintype "passive"))
      (node (ref "con12") (pin "72") (pinfunction "72_72") (pintype "passive"))
    )
    (net (code "132") (name "WIFI_CLK") (class "Default")
      (node (ref "CON10") (pin "37") (pinfunction "37_37") (pintype "passive"))
    )
    (net (code "133") (name "WIFI_CMD") (class "Default")
      (node (ref "CON10") (pin "38") (pinfunction "38_38") (pintype "passive"))
    )
    (net (code "134") (name "WIFI_D0") (class "Default")
      (node (ref "CON10") (pin "41") (pinfunction "41_41") (pintype "passive"))
    )
    (net (code "135") (name "WIFI_D1") (class "Default")
      (node (ref "CON10") (pin "40") (pinfunction "40_40") (pintype "passive"))
    )
    (net (code "136") (name "WIFI_D2") (class "Default")
      (node (ref "CON10") (pin "43") (pinfunction "43_43") (pintype "passive"))
    )
    (net (code "137") (name "WIFI_D3") (class "Default")
      (node (ref "CON10") (pin "42") (pinfunction "42_42") (pintype "passive"))
    )
    (net (code "138") (name "WIFI_PWDN") (class "Default")
      (node (ref "CON10") (pin "36") (pinfunction "36_36") (pintype "passive"))
    )
    (net (code "139") (name "WIFI_WOW") (class "Default")
      (node (ref "CON10") (pin "35") (pinfunction "35_35") (pintype "passive"))
    )
    (net (code "140") (name "W_PMU_EN") (class "Default")
      (node (ref "CON13") (pin "8") (pinfunction "8_8") (pintype "passive"))
    )
    (net (code "141") (name "XCLKOUT") (class "Default")
      (node (ref "CON10") (pin "59") (pinfunction "59_59") (pintype "passive"))
    )
    (net (code "142") (name "XEINT1_BAK") (class "Default")
      (node (ref "CON13") (pin "16") (pinfunction "16_16") (pintype "passive"))
    )
    (net (code "143") (name "XEINT6") (class "Default")
      (node (ref "CON13") (pin "18") (pinfunction "18_18") (pintype "passive"))
      (node (ref "R5") (pin "2") (pinfunction "2_2") (pintype "passive"))
      (node (ref "SW2") (pin "4") (pinfunction "4_4") (pintype "passive"))
    )
    (net (code "144") (name "XEINT7{slash}GPX0_7") (class "Default")
      (node (ref "CON10") (pin "32") (pinfunction "32_32") (pintype "passive"))
    )
    (net (code "145") (name "XEINT14_BAK") (class "Default")
      (node (ref "CON13") (pin "22") (pinfunction "22_22") (pintype "passive"))
    )
    (net (code "146") (name "XEINT18{slash}KP_ROW2{slash}ALV_DBG14") (class "Default")
      (node (ref "CON10") (pin "48") (pinfunction "48_48") (pintype "passive"))
    )
    (net (code "147") (name "XEINT29{slash}KP_ROW13{slash}ALV_DBG25") (class "Default")
      (node (ref "CON10") (pin "49") (pinfunction "49_49") (pintype "passive"))
    )
    (net (code "148") (name "XEINT30{slash}HDMI_CEC{slash}ALV_DBG26") (class "Default")
      (node (ref "CON11") (pin "22") (pinfunction "22_22") (pintype "passive"))
    )
    (net (code "149") (name "XOM2") (class "Default")
      (node (ref "CON13") (pin "9") (pinfunction "9_9") (pintype "passive"))
      (node (ref "SW2") (pin "1") (pinfunction "1_1") (pintype "passive"))
    )
    (net (code "150") (name "XOM3") (class "Default")
      (node (ref "CON13") (pin "10") (pinfunction "10_10") (pintype "passive"))
      (node (ref "CON13") (pin "11") (pinfunction "11_11") (pintype "passive"))
      (node (ref "SW2") (pin "2") (pinfunction "2_2") (pintype "passive"))
    )
    (net (code "151") (name "XPWMTOUT1") (class "Default")
      (node (ref "CON13") (pin "5") (pinfunction "5_5") (pintype "passive"))
    )
    (net (code "152") (name "XUCTS1") (class "Default")
      (node (ref "con12") (pin "65") (pinfunction "65_65") (pintype "passive"))
    )
    (net (code "153") (name "XUHOSTDATA0") (class "Default")
      (node (ref "CON10") (pin "77") (pinfunction "77_77") (pintype "passive"))
    )
    (net (code "154") (name "XUHOSTDATA1_EXT") (class "Default")
      (node (ref "CON10") (pin "9") (pinfunction "9_9") (pintype "passive"))
    )
    (net (code "155") (name "XUHOSTSTROBE0") (class "Default")
      (node (ref "CON10") (pin "78") (pinfunction "78_78") (pintype "passive"))
    )
    (net (code "156") (name "XUHOSTSTROBE1_EXT") (class "Default")
      (node (ref "CON10") (pin "10") (pinfunction "10_10") (pintype "passive"))
    )
    (net (code "157") (name "XURTS1") (class "Default")
      (node (ref "con12") (pin "62") (pinfunction "62_62") (pintype "passive"))
    )
    (net (code "158") (name "XadcAIN0") (class "Default")
      (node (ref "CON11") (pin "49") (pinfunction "49_49") (pintype "passive"))
    )
    (net (code "159") (name "XadcAIN1") (class "Default")
      (node (ref "CON11") (pin "51") (pinfunction "51_51") (pintype "passive"))
    )
    (net (code "160") (name "XadcAIN2") (class "Default")
      (node (ref "CON11") (pin "53") (pinfunction "53_53") (pintype "passive"))
    )
    (net (code "161") (name "XadcAIN3") (class "Default")
      (node (ref "CON11") (pin "55") (pinfunction "55_55") (pintype "passive"))
    )
    (net (code "162") (name "XciFIELD") (class "Default")
      (node (ref "CON11") (pin "40") (pinfunction "40_40") (pintype "passive"))
    )
    (net (code "163") (name "XhdmiTX0N") (class "Default")
      (node (ref "CON11") (pin "9") (pinfunction "9_9") (pintype "passive"))
    )
    (net (code "164") (name "XhdmiTX0P") (class "Default")
      (node (ref "CON11") (pin "7") (pinfunction "7_7") (pintype "passive"))
    )
    (net (code "165") (name "XhdmiTX1N") (class "Default")
      (node (ref "CON11") (pin "10") (pinfunction "10_10") (pintype "passive"))
    )
    (net (code "166") (name "XhdmiTX1P") (class "Default")
      (node (ref "CON11") (pin "8") (pinfunction "8_8") (pintype "passive"))
    )
    (net (code "167") (name "XhdmiTX2N") (class "Default")
      (node (ref "CON11") (pin "15") (pinfunction "15_15") (pintype "passive"))
    )
    (net (code "168") (name "XhdmiTX2P") (class "Default")
      (node (ref "CON11") (pin "13") (pinfunction "13_13") (pintype "passive"))
    )
    (net (code "169") (name "XhdmiTXCN") (class "Default")
      (node (ref "CON11") (pin "16") (pinfunction "16_16") (pintype "passive"))
    )
    (net (code "170") (name "XhdmiTXCP") (class "Default")
      (node (ref "CON11") (pin "14") (pinfunction "14_14") (pintype "passive"))
    )
    (net (code "171") (name "Xi2s0CDCLK{slash}PCM_0_EXTCLK") (class "Default")
      (node (ref "CON11") (pin "71") (pinfunction "71_71") (pintype "passive"))
    )
    (net (code "172") (name "Xi2s0LRCK{slash}PCM_0_FSYNC") (class "Default")
      (node (ref "CON11") (pin "70") (pinfunction "70_70") (pintype "passive"))
    )
    (net (code "173") (name "Xi2s0SCLK{slash}PCM_0_SCLK") (class "Default")
      (node (ref "CON11") (pin "68") (pinfunction "68_68") (pintype "passive"))
    )
    (net (code "174") (name "Xi2s0SDI{slash}PCM_0_SIN") (class "Default")
      (node (ref "CON11") (pin "74") (pinfunction "74_74") (pintype "passive"))
    )
    (net (code "175") (name "Xi2s0SDO_0{slash}PCM_0_SOUT") (class "Default")
      (node (ref "CON11") (pin "72") (pinfunction "72_72") (pintype "passive"))
    )
    (net (code "176") (name "XispI2C1SCL") (class "Default")
      (node (ref "CON13") (pin "30") (pinfunction "30_30") (pintype "passive"))
    )
    (net (code "177") (name "XispI2C1SDA") (class "Default")
      (node (ref "CON13") (pin "32") (pinfunction "32_32") (pintype "passive"))
    )
    (net (code "178") (name "XispSPICLK") (class "Default")
      (node (ref "CON13") (pin "26") (pinfunction "26_26") (pintype "passive"))
    )
    (net (code "179") (name "XispSPICSn") (class "Default")
      (node (ref "CON13") (pin "19") (pinfunction "19_19") (pintype "passive"))
    )
    (net (code "180") (name "XispSPIMISO") (class "Default")
      (node (ref "CON13") (pin "21") (pinfunction "21_21") (pintype "passive"))
    )
    (net (code "181") (name "XispSPIMOSI") (class "Default")
      (node (ref "CON13") (pin "28") (pinfunction "28_28") (pintype "passive"))
    )
    (net (code "182") (name "XjTCK") (class "Default")
      (node (ref "CON13") (pin "13") (pinfunction "13_13") (pintype "passive"))
    )
    (net (code "183") (name "XjTDI") (class "Default")
      (node (ref "CON13") (pin "14") (pinfunction "14_14") (pintype "passive"))
    )
    (net (code "184") (name "XjTDO") (class "Default")
      (node (ref "CON13") (pin "15") (pinfunction "15_15") (pintype "passive"))
    )
    (net (code "185") (name "XjTMS") (class "Default")
      (node (ref "CON13") (pin "12") (pinfunction "12_12") (pintype "passive"))
    )
    (net (code "186") (name "XjTRSTn") (class "Default")
      (node (ref "CON13") (pin "17") (pinfunction "17_17") (pintype "passive"))
    )
    (net (code "187") (name "Xm0ADDR0") (class "Default")
      (node (ref "CON13") (pin "65") (pinfunction "65_65") (pintype "passive"))
    )
    (net (code "188") (name "Xm0ADDR1") (class "Default")
      (node (ref "CON13") (pin "68") (pinfunction "68_68") (pintype "passive"))
    )
    (net (code "189") (name "Xm0ADDR2") (class "Default")
      (node (ref "CON13") (pin "67") (pinfunction "67_67") (pintype "passive"))
    )
    (net (code "190") (name "Xm0ADDR3") (class "Default")
      (node (ref "CON13") (pin "70") (pinfunction "70_70") (pintype "passive"))
    )
    (net (code "191") (name "Xm0ADDR4") (class "Default")
      (node (ref "CON13") (pin "69") (pinfunction "69_69") (pintype "passive"))
    )
    (net (code "192") (name "Xm0ADDR5") (class "Default")
      (node (ref "CON13") (pin "72") (pinfunction "72_72") (pintype "passive"))
    )
    (net (code "193") (name "Xm0ADDR6") (class "Default")
      (node (ref "CON13") (pin "71") (pinfunction "71_71") (pintype "passive"))
    )
    (net (code "194") (name "Xm0ADDR7") (class "Default")
      (node (ref "CON13") (pin "74") (pinfunction "74_74") (pintype "passive"))
    )
    (net (code "196") (name "Xm0BEn0") (class "Default")
      (node (ref "CON13") (pin "43") (pinfunction "43_43") (pintype "passive"))
    )
    (net (code "197") (name "Xm0DATA0") (class "Default")
      (node (ref "CON13") (pin "45") (pinfunction "45_45") (pintype "passive"))
    )
    (net (code "198") (name "Xm0DATA1") (class "Default")
      (node (ref "CON13") (pin "50") (pinfunction "50_50") (pintype "passive"))
    )
    (net (code "199") (name "Xm0DATA2") (class "Default")
      (node (ref "CON13") (pin "47") (pinfunction "47_47") (pintype "passive"))
    )
    (net (code "200") (name "Xm0DATA3") (class "Default")
      (node (ref "CON13") (pin "52") (pinfunction "52_52") (pintype "passive"))
    )
    (net (code "201") (name "Xm0DATA4") (class "Default")
      (node (ref "CON13") (pin "49") (pinfunction "49_49") (pintype "passive"))
    )
    (net (code "202") (name "Xm0DATA5") (class "Default")
      (node (ref "CON13") (pin "54") (pinfunction "54_54") (pintype "passive"))
    )
    (net (code "203") (name "Xm0DATA6") (class "Default")
      (node (ref "CON13") (pin "51") (pinfunction "51_51") (pintype "passive"))
    )
    (net (code "204") (name "Xm0DATA7") (class "Default")
      (node (ref "CON13") (pin "56") (pinfunction "56_56") (pintype "passive"))
    )
    (net (code "205") (name "Xm0DATA8") (class "Default")
      (node (ref "CON13") (pin "55") (pinfunction "55_55") (pintype "passive"))
    )
    (net (code "206") (name "Xm0DATA9") (class "Default")
      (node (ref "CON13") (pin "58") (pinfunction "58_58") (pintype "passive"))
    )
    (net (code "207") (name "Xm0DATA10") (class "Default")
      (node (ref "CON13") (pin "57") (pinfunction "57_57") (pintype "passive"))
    )
    (net (code "208") (name "Xm0DATA11") (class "Default")
      (node (ref "CON13") (pin "60") (pinfunction "60_60") (pintype "passive"))
    )
    (net (code "209") (name "Xm0DATA12") (class "Default")
      (node (ref "CON13") (pin "59") (pinfunction "59_59") (pintype "passive"))
    )
    (net (code "210") (name "Xm0DATA13") (class "Default")
      (node (ref "CON13") (pin "62") (pinfunction "62_62") (pintype "passive"))
    )
    (net (code "211") (name "Xm0DATA14") (class "Default")
      (node (ref "CON13") (pin "61") (pinfunction "61_61") (pintype "passive"))
    )
    (net (code "212") (name "Xm0DATA15") (class "Default")
      (node (ref "CON13") (pin "64") (pinfunction "64_64") (pintype "passive"))
    )
    (net (code "214") (name "Xm0DATA_RDn") (class "Default")
      (node (ref "CON13") (pin "44") (pinfunction "44_44") (pintype "passive"))
    )
    (net (code "215") (name "Xm0OEn") (class "Default")
      (node (ref "CON13") (pin "48") (pinfunction "48_48") (pintype "passive"))
    )
    (net (code "216") (name "Xm0WEn") (class "Default")
      (node (ref "CON13") (pin "41") (pinfunction "41_41") (pintype "passive"))
    )
    (net (code "217") (name "Xm0cs0") (class "Default")
      (node (ref "CON13") (pin "73") (pinfunction "73_73") (pintype "passive"))
    )
    (net (code "218") (name "Xm0cs1") (class "Default")
      (node (ref "CON13") (pin "46") (pinfunction "46_46") (pintype "passive"))
    )
    (net (code "219") (name "Xmipi2LSDN0") (class "Default")
      (node (ref "CON11") (pin "64") (pinfunction "64_64") (pintype "passive"))
    )
    (net (code "220") (name "Xmipi2LSDN1") (class "Default")
      (node (ref "CON11") (pin "67") (pinfunction "67_67") (pintype "passive"))
    )
    (net (code "221") (name "Xmipi2LSDNCLK") (class "Default")
      (node (ref "CON11") (pin "61") (pinfunction "61_61") (pintype "passive"))
    )
    (net (code "222") (name "Xmipi2LSDP0") (class "Default")
      (node (ref "CON11") (pin "62") (pinfunction "62_62") (pintype "passive"))
    )
    (net (code "223") (name "Xmipi2LSDP1") (class "Default")
      (node (ref "CON11") (pin "65") (pinfunction "65_65") (pintype "passive"))
    )
    (net (code "224") (name "Xmipi2LSDPCLK") (class "Default")
      (node (ref "CON11") (pin "59") (pinfunction "59_59") (pintype "passive"))
    )
    (net (code "225") (name "XmipiMDN0") (class "Default")
      (node (ref "CON13") (pin "29") (pinfunction "29_29") (pintype "passive"))
    )
    (net (code "226") (name "XmipiMDN1") (class "Default")
      (node (ref "CON13") (pin "33") (pinfunction "33_33") (pintype "passive"))
    )
    (net (code "227") (name "XmipiMDN2") (class "Default")
      (node (ref "CON13") (pin "38") (pinfunction "38_38") (pintype "passive"))
    )
    (net (code "228") (name "XmipiMDN3") (class "Default")
      (node (ref "CON13") (pin "42") (pinfunction "42_42") (pintype "passive"))
    )
    (net (code "229") (name "XmipiMDNCLK") (class "Default")
      (node (ref "CON13") (pin "37") (pinfunction "37_37") (pintype "passive"))
    )
    (net (code "230") (name "XmipiMDP0") (class "Default")
      (node (ref "CON13") (pin "27") (pinfunction "27_27") (pintype "passive"))
    )
    (net (code "231") (name "XmipiMDP1") (class "Default")
      (node (ref "CON13") (pin "31") (pinfunction "31_31") (pintype "passive"))
    )
    (net (code "232") (name "XmipiMDP2") (class "Default")
      (node (ref "CON13") (pin "36") (pinfunction "36_36") (pintype "passive"))
    )
    (net (code "233") (name "XmipiMDP3") (class "Default")
      (node (ref "CON13") (pin "40") (pinfunction "40_40") (pintype "passive"))
    )
    (net (code "234") (name "XmipiMDPCLK") (class "Default")
      (node (ref "CON13") (pin "35") (pinfunction "35_35") (pintype "passive"))
    )
    (net (code "235") (name "Xmmc2CLK") (class "Default")
      (node (ref "CON10") (pin "26") (pinfunction "26_26") (pintype "passive"))
    )
    (net (code "236") (name "Xmmc2CMD") (class "Default")
      (node (ref "CON10") (pin "23") (pinfunction "23_23") (pintype "passive"))
    )
    (net (code "237") (name "Xmmc2DATA0") (class "Default")
      (node (ref "CON10") (pin "28") (pinfunction "28_28") (pintype "passive"))
    )
    (net (code "238") (name "Xmmc2DATA1") (class "Default")
      (node (ref "CON10") (pin "30") (pinfunction "30_30") (pintype "passive"))
    )
    (net (code "239") (name "Xmmc2DATA2") (class "Default")
      (node (ref "CON10") (pin "25") (pinfunction "25_25") (pintype "passive"))
    )
    (net (code "240") (name "Xmmc2DATA3") (class "Default")
      (node (ref "CON10") (pin "27") (pinfunction "27_27") (pintype "passive"))
    )
    (net (code "241") (name "XnRESET_EXT") (class "Default")
      (node (ref "CON10") (pin "61") (pinfunction "61_61") (pintype "passive"))
    )
    (net (code "242") (name "XnRSOUT") (class "Default")
      (node (ref "CON10") (pin "64") (pinfunction "64_64") (pintype "passive"))
    )
    (net (code "243") (name "XnWRESET") (class "Default")
      (node (ref "CON10") (pin "62") (pinfunction "62_62") (pintype "passive"))
    )
    (net (code "244") (name "XspiCLK0{slash}I2C_4_SDA") (class "Default")
      (node (ref "CON11") (pin "73") (pinfunction "73_73") (pintype "passive"))
    )
    (net (code "245") (name "XspiCSn0{slash}I2C_4_SCL") (class "Default")
      (node (ref "CON11") (pin "76") (pinfunction "76_76") (pintype "passive"))
    )
    (net (code "246") (name "XuCTSn0") (class "Default")
      (node (ref "CON10") (pin "46") (pinfunction "46_46") (pintype "passive"))
    )
    (net (code "247") (name "XuCTSn2{slash}I2C_3_SDA") (class "Default")
      (node (ref "con12") (pin "51") (pinfunction "51_51") (pintype "passive"))
    )
    (net (code "248") (name "XuRTSn0") (class "Default")
      (node (ref "CON10") (pin "47") (pinfunction "47_47") (pintype "passive"))
    )
    (net (code "249") (name "XuRTSn2{slash}I2C_3_SCL") (class "Default")
      (node (ref "con12") (pin "49") (pinfunction "49_49") (pintype "passive"))
    )
    (net (code "250") (name "XuRXD0") (class "Default")
      (node (ref "CON10") (pin "44") (pinfunction "44_44") (pintype "passive"))
    )
    (net (code "251") (name "XuRXD1") (class "Default")
      (node (ref "con12") (pin "60") (pinfunction "60_60") (pintype "passive"))
    )
    (net (code "252") (name "XuRXD2{slash}UART_AUDIO_RXD") (class "Default")
      (node (ref "con12") (pin "54") (pinfunction "54_54") (pintype "passive"))
    )
    (net (code "253") (name "XuTXD0") (class "Default")
      (node (ref "CON10") (pin "45") (pinfunction "45_45") (pintype "passive"))
    )
    (net (code "254") (name "XuTXD1") (class "Default")
      (node (ref "con12") (pin "63") (pinfunction "63_63") (pintype "passive"))
    )
    (net (code "255") (name "XuTXD2{slash}UART_AUDIO_TXD") (class "Default")
      (node (ref "con12") (pin "56") (pinfunction "56_56") (pintype "passive"))
    )
    (net (code "256") (name "XuotgDM") (class "Default")
      (node (ref "CON10") (pin "16") (pinfunction "16_16") (pintype "passive"))
    )
    (net (code "257") (name "XuotgDP") (class "Default")
      (node (ref "CON10") (pin "14") (pinfunction "14_14") (pintype "passive"))
    )
    (net (code "258") (name "XuotgID") (class "Default")
      (node (ref "CON10") (pin "12") (pinfunction "12_12") (pintype "passive"))
    )
    (net (code "259") (name "XuotgVBUS") (class "Default")
      (node (ref "CON11") (pin "24") (pinfunction "24_24") (pintype "passive"))
    )
    (net (code "260") (name "XvSYS_OE") (class "Default")
      (node (ref "CON13") (pin "39") (pinfunction "39_39") (pintype "passive"))
    )
    (net (code "261") (name "XvVSYNC_LDI") (class "Default")
      (node (ref "CON13") (pin "34") (pinfunction "34_34") (pintype "passive"))
    )
    (net (code "262") (name "unconnected-(U22-PGOOD-Pad8)") (class "Default")
      (node (ref "U22") (pin "8") (pinfunction "PGOOD_8") (pintype "passive"))
    )
    (net (code "263") (name "unconnected-(con12-Pad11)") (class "Default")
      (node (ref "con12") (pin "11") (pinfunction "11_11") (pintype "passive"))
    )
    (net (code "264") (name "unconnected-(con12-Pad13)") (class "Default")
      (node (ref "con12") (pin "13") (pinfunction "13_13") (pintype "passive"))
    )
    (net (code "265") (name "unconnected-(con12-Pad71)") (class "Default")
      (node (ref "con12") (pin "71") (pinfunction "71_71") (pintype "passive"))
    )
    (net (code "266") (name "unconnected-(con12-Pad73)") (class "Default")
      (node (ref "con12") (pin "73") (pinfunction "73_73") (pintype "passive"))
    )
  )
)
